# pico.net
KiCad netlist of a schematic drawn in EAGLE
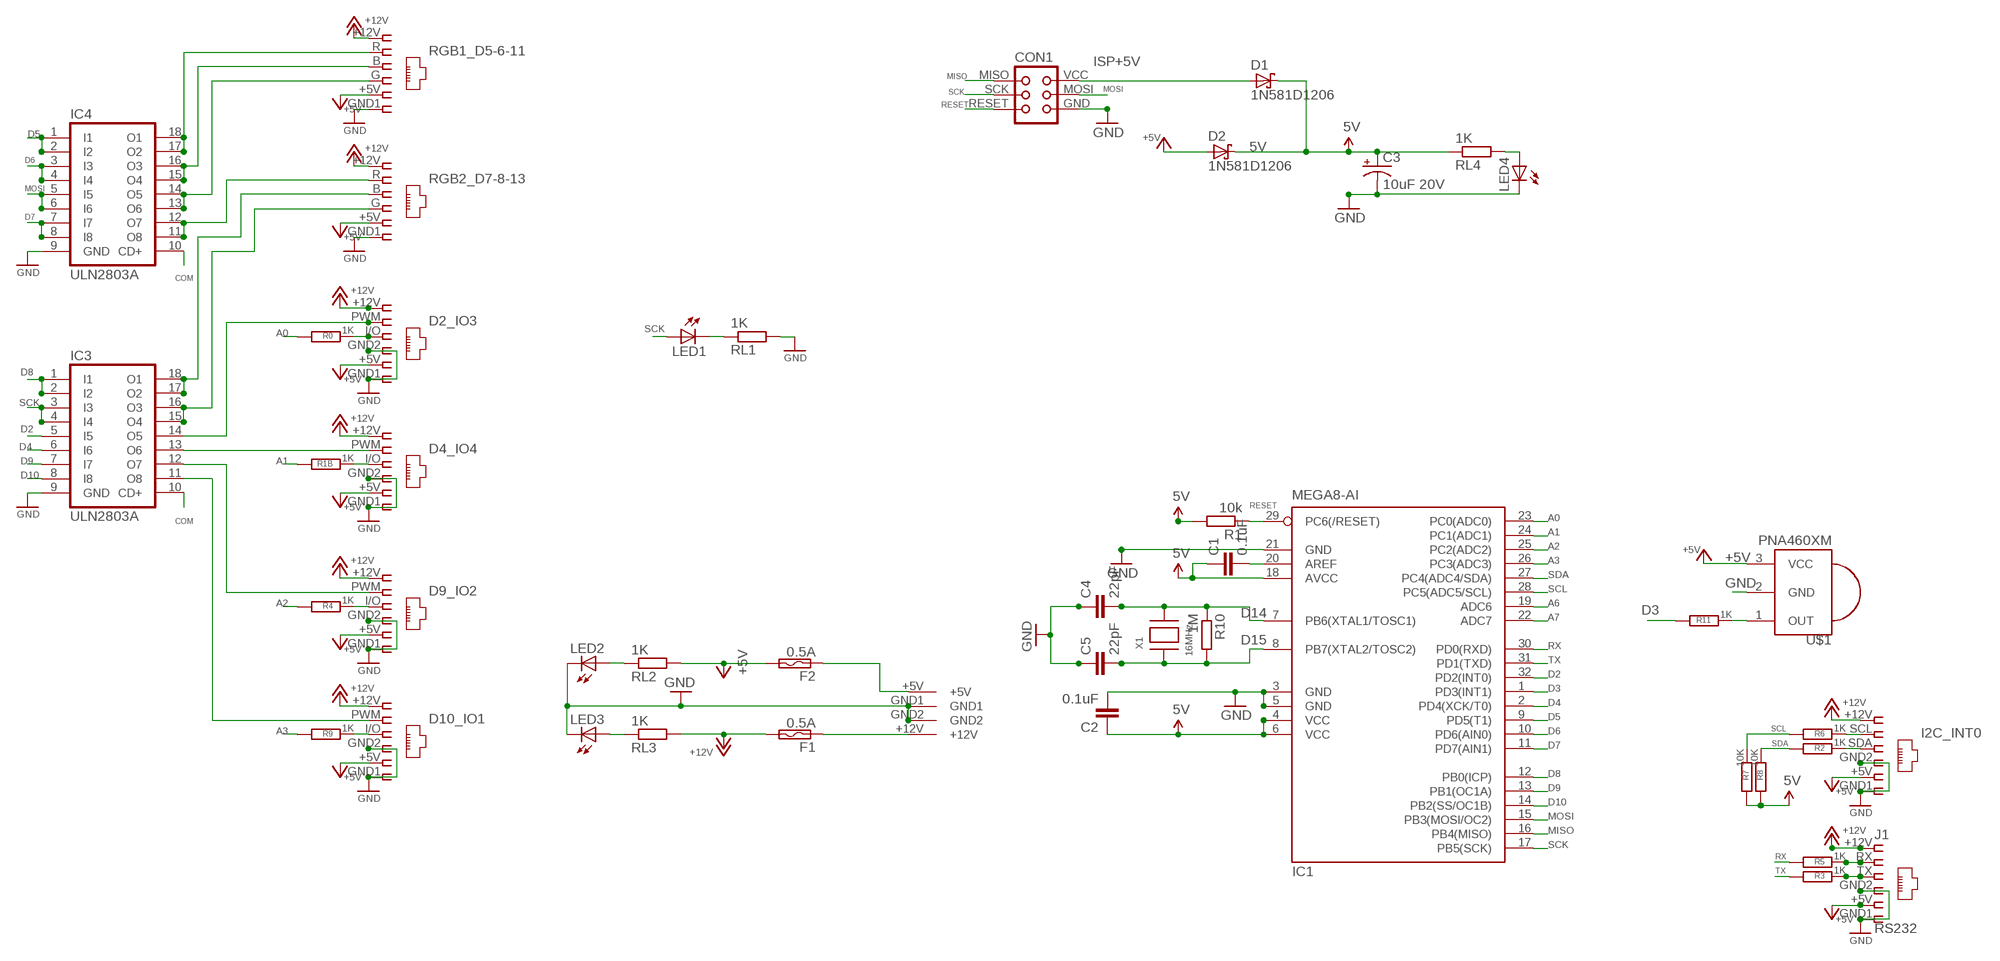
[diagram p0: schematic, sheet 1]

(export (version "E")
  (design (tool "Eeschema 10.0.6"))
  (components
    (comp (ref "C1")
      (value "0.1uF")
      (footprint "eagle-import:C1206")
      (libsource (lib "eagle-import") (part "C-EUC1206"))
    )
    (comp (ref "C2")
      (value "0.1uF")
      (footprint "eagle-import:C1206")
      (libsource (lib "eagle-import") (part "C-EUC1206"))
    )
    (comp (ref "C3")
      (value "10uF 20V")
      (footprint "eagle-import:EIA3216-KIT")
      (libsource (lib "eagle-import") (part "CAP_POL1206-KIT"))
    )
    (comp (ref "C4")
      (value "22pF")
      (footprint "eagle-import:C1206")
      (libsource (lib "eagle-import") (part "C-EUC1206"))
    )
    (comp (ref "C5")
      (value "22pF")
      (footprint "eagle-import:C1206")
      (libsource (lib "eagle-import") (part "C-EUC1206"))
    )
    (comp (ref "CON1")
      (value "TINYISP")
      (footprint "eagle-import:TINYISP")
      (libsource (lib "eagle-import") (part "TINYISP"))
    )
    (comp (ref "D1")
      (value "1N581D1206")
      (footprint "eagle-import:LED-1206")
      (libsource (lib "eagle-import") (part "1N581D1206"))
    )
    (comp (ref "D2")
      (value "1N581D1206")
      (footprint "eagle-import:LED-1206")
      (libsource (lib "eagle-import") (part "1N581D1206"))
    )
    (comp (ref "D2_IO3")
      (value "IO3")
      (footprint "eagle-import:RJ12-STRAIGHT")
      (libsource (lib "eagle-import") (part "RJ12STRAIGHT"))
    )
    (comp (ref "D4_IO4")
      (value "IO4")
      (footprint "eagle-import:RJ12-STRAIGHT")
      (libsource (lib "eagle-import") (part "RJ12STRAIGHT"))
    )
    (comp (ref "D9_IO2")
      (value "IO2")
      (footprint "eagle-import:RJ12-STRAIGHT")
      (libsource (lib "eagle-import") (part "RJ12STRAIGHT"))
    )
    (comp (ref "D10_IO1")
      (value "IO1")
      (footprint "eagle-import:RJ12-STRAIGHT")
      (libsource (lib "eagle-import") (part "RJ12STRAIGHT"))
    )
    (comp (ref "F1")
      (value "0.5A")
      (footprint "eagle-import:C1812")
      (libsource (lib "eagle-import") (part "POLYSWITCHSMD1812"))
    )
    (comp (ref "F2")
      (value "0.5A")
      (footprint "eagle-import:C1812")
      (libsource (lib "eagle-import") (part "POLYSWITCHSMD1812"))
    )
    (comp (ref "I2C_INT0")
      (value "I2C")
      (footprint "eagle-import:RJ12-STRAIGHT-I2C")
      (libsource (lib "eagle-import") (part "RJ12STRAIGHT-I2C"))
    )
    (comp (ref "IC1")
      (value "MEGA8-AI")
      (footprint "eagle-import:TQFP32-08")
      (fields (field (name "MPN") "ATMEGA8-16AU"))
      (libsource (lib "eagle-import") (part "MEGA8-AI"))
    )
    (comp (ref "IC3")
      (value "ULN2803A")
      (footprint "eagle-import:SO18W")
      (libsource (lib "eagle-import") (part "ULN2803A"))
    )
    (comp (ref "IC4")
      (value "ULN2803A")
      (footprint "eagle-import:SO18W")
      (libsource (lib "eagle-import") (part "ULN2803A"))
    )
    (comp (ref "J1")
      (value "RS232")
      (footprint "eagle-import:RJ12-STRAIGHT-RS232")
      (libsource (lib "eagle-import") (part "RJ12STRAIGHT-RS232-SERVER"))
    )
    (comp (ref "LED1")
      (value "LED3MM")
      (footprint "eagle-import:LED3MM")
      (libsource (lib "eagle-import") (part "LED3MM"))
    )
    (comp (ref "LED2")
      (value "LED3MM")
      (footprint "eagle-import:LED3MM")
      (libsource (lib "eagle-import") (part "LED3MM"))
    )
    (comp (ref "LED3")
      (value "LED3MM")
      (footprint "eagle-import:LED3MM")
      (libsource (lib "eagle-import") (part "LED3MM"))
    )
    (comp (ref "LED4")
      (value "LED3MM")
      (footprint "eagle-import:LED3MM")
      (libsource (lib "eagle-import") (part "LED3MM"))
    )
    (comp (ref "R0")
      (value "1K")
      (footprint "eagle-import:M1206")
      (libsource (lib "eagle-import") (part "R-EU_M1206"))
    )
    (comp (ref "R1")
      (value "10k")
      (footprint "eagle-import:M1206")
      (libsource (lib "eagle-import") (part "R-EU_M1206"))
    )
    (comp (ref "R1B")
      (value "1K")
      (footprint "eagle-import:M1206")
      (libsource (lib "eagle-import") (part "R-EU_M1206"))
    )
    (comp (ref "R2")
      (value "1K")
      (footprint "eagle-import:M1206")
      (libsource (lib "eagle-import") (part "R-EU_M1206"))
    )
    (comp (ref "R3")
      (value "1K")
      (footprint "eagle-import:M1206")
      (libsource (lib "eagle-import") (part "R-EU_M1206"))
    )
    (comp (ref "R4")
      (value "1K")
      (footprint "eagle-import:M1206")
      (libsource (lib "eagle-import") (part "R-EU_M1206"))
    )
    (comp (ref "R5")
      (value "1K")
      (footprint "eagle-import:M1206")
      (libsource (lib "eagle-import") (part "R-EU_M1206"))
    )
    (comp (ref "R6")
      (value "1K")
      (footprint "eagle-import:M1206")
      (libsource (lib "eagle-import") (part "R-EU_M1206"))
    )
    (comp (ref "R7")
      (value "10K")
      (footprint "eagle-import:M1206")
      (libsource (lib "eagle-import") (part "R-EU_M1206"))
    )
    (comp (ref "R8")
      (value "10K")
      (footprint "eagle-import:M1206")
      (libsource (lib "eagle-import") (part "R-EU_M1206"))
    )
    (comp (ref "R9")
      (value "1K")
      (footprint "eagle-import:M1206")
      (libsource (lib "eagle-import") (part "R-EU_M1206"))
    )
    (comp (ref "R10")
      (value "1M")
      (footprint "eagle-import:M1206")
      (libsource (lib "eagle-import") (part "R-EU_M1206"))
    )
    (comp (ref "R11")
      (value "1K")
      (footprint "eagle-import:M1206")
      (libsource (lib "eagle-import") (part "R-EU_M1206"))
    )
    (comp (ref "RGB1_D5-6-11")
      (value "RGB1")
      (footprint "eagle-import:RJ12-STRAIGHT-RGB")
      (libsource (lib "eagle-import") (part "RJ12STRAIGHT-RGB"))
    )
    (comp (ref "RGB2_D7-8-13")
      (value "RGB2")
      (footprint "eagle-import:RJ12-STRAIGHT-RGB")
      (libsource (lib "eagle-import") (part "RJ12STRAIGHT-RGB"))
    )
    (comp (ref "RL1")
      (value "1K")
      (footprint "eagle-import:M1206")
      (libsource (lib "eagle-import") (part "R-EU_M1206"))
    )
    (comp (ref "RL2")
      (value "1K")
      (footprint "eagle-import:M1206")
      (libsource (lib "eagle-import") (part "R-EU_M1206"))
    )
    (comp (ref "RL3")
      (value "1K")
      (footprint "eagle-import:M1206")
      (libsource (lib "eagle-import") (part "R-EU_M1206"))
    )
    (comp (ref "RL4")
      (value "1K")
      (footprint "eagle-import:M1206")
      (libsource (lib "eagle-import") (part "R-EU_M1206"))
    )
    (comp (ref "U$1")
      (value "PNA460XM")
      (footprint "eagle-import:PNA460XM")
      (libsource (lib "eagle-import") (part "PNA460XM"))
    )
    (comp (ref "U$2")
      (value "KPJX-4S-S")
      (footprint "eagle-import:KPJX-4S-S")
      (libsource (lib "eagle-import") (part "KPJX-4S-S"))
    )
    (comp (ref "X1")
      (value "16MHz")
      (footprint "eagle-import:NX6035")
      (libsource (lib "eagle-import") (part "XTALNX6035"))
    )
  )
  (nets
    (net (code "1") (name "+5V") (class "Default")
      (node (ref "D10_IO1") (pin "+5V") (pinfunction "5_+5V") (pintype "power_in"))
      (node (ref "D2") (pin "A") (pinfunction "A_A") (pintype "passive"))
      (node (ref "D2_IO3") (pin "+5V") (pinfunction "5_+5V") (pintype "power_in"))
      (node (ref "D4_IO4") (pin "+5V") (pinfunction "5_+5V") (pintype "power_in"))
      (node (ref "D9_IO2") (pin "+5V") (pinfunction "5_+5V") (pintype "power_in"))
      (node (ref "F2") (pin "2") (pinfunction "2_2") (pintype "passive"))
      (node (ref "I2C_INT0") (pin "+5V") (pinfunction "5_+5V") (pintype "power_in"))
      (node (ref "J1") (pin "+5V") (pinfunction "5_+5V") (pintype "power_in"))
      (node (ref "RGB1_D5-6-11") (pin "+5V") (pinfunction "5_+5V") (pintype "power_in"))
      (node (ref "RGB2_D7-8-13") (pin "+5V") (pinfunction "5_+5V") (pintype "power_in"))
      (node (ref "RL2") (pin "2") (pinfunction "2_2") (pintype "passive"))
      (node (ref "U$1") (pin "3") (pinfunction "VCC_3") (pintype "power_in"))
    )
    (net (code "2") (name "+12V") (class "Default")
      (node (ref "D10_IO1") (pin "+12V") (pinfunction "1_+12V") (pintype "power_in"))
      (node (ref "D2_IO3") (pin "+12V") (pinfunction "1_+12V") (pintype "power_in"))
      (node (ref "D4_IO4") (pin "+12V") (pinfunction "1_+12V") (pintype "power_in"))
      (node (ref "D9_IO2") (pin "+12V") (pinfunction "1_+12V") (pintype "power_in"))
      (node (ref "F1") (pin "2") (pinfunction "2_2") (pintype "passive"))
      (node (ref "I2C_INT0") (pin "+12V") (pinfunction "1_+12V") (pintype "power_in"))
      (node (ref "J1") (pin "+12V") (pinfunction "1_+12V") (pintype "power_in"))
      (node (ref "RGB1_D5-6-11") (pin "+12V") (pinfunction "1_+12V") (pintype "power_in"))
      (node (ref "RGB2_D7-8-13") (pin "+12V") (pinfunction "1_+12V") (pintype "power_in"))
      (node (ref "RL3") (pin "2") (pinfunction "2_2") (pintype "passive"))
    )
    (net (code "3") (name "/A0") (class "Default")
      (node (ref "IC1") (pin "23") (pinfunction "PC0(ADC0)_23") (pintype "bidirectional"))
      (node (ref "R0") (pin "2") (pinfunction "2_2") (pintype "passive"))
    )
    (net (code "4") (name "/A1") (class "Default")
      (node (ref "IC1") (pin "24") (pinfunction "PC1(ADC1)_24") (pintype "bidirectional"))
      (node (ref "R1B") (pin "2") (pinfunction "2_2") (pintype "passive"))
    )
    (net (code "5") (name "/A2") (class "Default")
      (node (ref "IC1") (pin "25") (pinfunction "PC2(ADC2)_25") (pintype "bidirectional"))
      (node (ref "R4") (pin "2") (pinfunction "2_2") (pintype "passive"))
    )
    (net (code "6") (name "/A3") (class "Default")
      (node (ref "IC1") (pin "26") (pinfunction "PC3(ADC3)_26") (pintype "bidirectional"))
      (node (ref "R9") (pin "2") (pinfunction "2_2") (pintype "passive"))
    )
    (net (code "7") (name "/A6") (class "Default")
      (node (ref "IC1") (pin "19") (pinfunction "ADC6_19") (pintype "bidirectional"))
    )
    (net (code "8") (name "/A7") (class "Default")
      (node (ref "IC1") (pin "22") (pinfunction "ADC7_22") (pintype "bidirectional"))
    )
    (net (code "9") (name "/COM") (class "Default")
      (node (ref "IC3") (pin "10") (pinfunction "CD+_10") (pintype "passive"))
      (node (ref "IC4") (pin "10") (pinfunction "CD+_10") (pintype "passive"))
    )
    (net (code "10") (name "/D2") (class "Default")
      (node (ref "IC1") (pin "32") (pinfunction "PD2(INT0)_32") (pintype "bidirectional"))
      (node (ref "IC3") (pin "5") (pinfunction "I5_5") (pintype "input"))
    )
    (net (code "11") (name "/D3") (class "Default")
      (node (ref "IC1") (pin "1") (pinfunction "PD3(INT1)_1") (pintype "bidirectional"))
      (node (ref "R11") (pin "2") (pinfunction "2_2") (pintype "passive"))
    )
    (net (code "12") (name "/D4") (class "Default")
      (node (ref "IC1") (pin "2") (pinfunction "PD4(XCK/T0)_2") (pintype "bidirectional"))
      (node (ref "IC3") (pin "6") (pinfunction "I6_6") (pintype "input"))
    )
    (net (code "13") (name "/D5") (class "Default")
      (node (ref "IC1") (pin "9") (pinfunction "PD5(T1)_9") (pintype "bidirectional"))
      (node (ref "IC4") (pin "1") (pinfunction "I1_1") (pintype "input"))
      (node (ref "IC4") (pin "2") (pinfunction "I2_2") (pintype "input"))
    )
    (net (code "14") (name "/D6") (class "Default")
      (node (ref "IC1") (pin "10") (pinfunction "PD6(AIN0)_10") (pintype "bidirectional"))
      (node (ref "IC4") (pin "3") (pinfunction "I3_3") (pintype "input"))
      (node (ref "IC4") (pin "4") (pinfunction "I4_4") (pintype "input"))
    )
    (net (code "15") (name "/D7") (class "Default")
      (node (ref "IC1") (pin "11") (pinfunction "PD7(AIN1)_11") (pintype "bidirectional"))
      (node (ref "IC4") (pin "7") (pinfunction "I7_7") (pintype "input"))
      (node (ref "IC4") (pin "8") (pinfunction "I8_8") (pintype "input"))
    )
    (net (code "16") (name "/D8") (class "Default")
      (node (ref "IC1") (pin "12") (pinfunction "PB0(ICP)_12") (pintype "bidirectional"))
      (node (ref "IC3") (pin "1") (pinfunction "I1_1") (pintype "input"))
      (node (ref "IC3") (pin "2") (pinfunction "I2_2") (pintype "input"))
    )
    (net (code "17") (name "/D9") (class "Default")
      (node (ref "IC1") (pin "13") (pinfunction "PB1(OC1A)_13") (pintype "bidirectional"))
      (node (ref "IC3") (pin "7") (pinfunction "I7_7") (pintype "input"))
    )
    (net (code "18") (name "/D10") (class "Default")
      (node (ref "IC1") (pin "14") (pinfunction "PB2(SS/OC1B)_14") (pintype "bidirectional"))
      (node (ref "IC3") (pin "8") (pinfunction "I8_8") (pintype "input"))
    )
    (net (code "19") (name "/D14") (class "Default")
      (node (ref "C4") (pin "2") (pinfunction "2_2") (pintype "passive"))
      (node (ref "IC1") (pin "7") (pinfunction "PB6(XTAL1/TOSC1)_7") (pintype "bidirectional"))
      (node (ref "R10") (pin "1") (pinfunction "1_1") (pintype "passive"))
      (node (ref "X1") (pin "P$2") (pinfunction "P$2_P$2") (pintype "bidirectional"))
    )
    (net (code "20") (name "/D15") (class "Default")
      (node (ref "C5") (pin "2") (pinfunction "2_2") (pintype "passive"))
      (node (ref "IC1") (pin "8") (pinfunction "PB7(XTAL2/TOSC2)_8") (pintype "bidirectional"))
      (node (ref "R10") (pin "2") (pinfunction "2_2") (pintype "passive"))
      (node (ref "X1") (pin "P$1") (pinfunction "P$1_P$1") (pintype "bidirectional"))
    )
    (net (code "21") (name "/ISP+5V") (class "Default")
      (node (ref "CON1") (pin "VCC") (pinfunction "VCC_VCC") (pintype "passive"))
      (node (ref "D1") (pin "A") (pinfunction "A_A") (pintype "passive"))
    )
    (net (code "22") (name "/MISO") (class "Default")
      (node (ref "CON1") (pin "MISO") (pinfunction "MISO_MISO") (pintype "passive"))
      (node (ref "IC1") (pin "16") (pinfunction "PB4(MISO)_16") (pintype "bidirectional"))
    )
    (net (code "23") (name "/MOSI") (class "Default")
      (node (ref "CON1") (pin "MOSI") (pinfunction "MOSI_MOSI") (pintype "passive"))
      (node (ref "IC1") (pin "15") (pinfunction "PB3(MOSI/OC2)_15") (pintype "bidirectional"))
      (node (ref "IC4") (pin "5") (pinfunction "I5_5") (pintype "input"))
      (node (ref "IC4") (pin "6") (pinfunction "I6_6") (pintype "input"))
    )
    (net (code "24") (name "/RESET") (class "Default")
      (node (ref "CON1") (pin "RESET") (pinfunction "RESET_RESET") (pintype "passive"))
      (node (ref "IC1") (pin "29") (pinfunction "PC6(/RESET)_29") (pintype "bidirectional"))
      (node (ref "R1") (pin "1") (pinfunction "1_1") (pintype "passive"))
    )
    (net (code "25") (name "/RX") (class "Default")
      (node (ref "IC1") (pin "30") (pinfunction "PD0(RXD)_30") (pintype "bidirectional"))
      (node (ref "R5") (pin "2") (pinfunction "2_2") (pintype "passive"))
    )
    (net (code "26") (name "/SCK") (class "Default")
      (node (ref "CON1") (pin "SCK") (pinfunction "SCK_SCK") (pintype "passive"))
      (node (ref "IC1") (pin "17") (pinfunction "PB5(SCK)_17") (pintype "bidirectional"))
      (node (ref "IC3") (pin "3") (pinfunction "I3_3") (pintype "input"))
      (node (ref "IC3") (pin "4") (pinfunction "I4_4") (pintype "input"))
      (node (ref "LED1") (pin "A") (pinfunction "A_A") (pintype "passive"))
    )
    (net (code "27") (name "/SCL") (class "Default")
      (node (ref "IC1") (pin "28") (pinfunction "PC5(ADC5/SCL)_28") (pintype "bidirectional"))
      (node (ref "R6") (pin "2") (pinfunction "2_2") (pintype "passive"))
      (node (ref "R7") (pin "1") (pinfunction "1_1") (pintype "passive"))
    )
    (net (code "28") (name "/SDA") (class "Default")
      (node (ref "IC1") (pin "27") (pinfunction "PC4(ADC4/SDA)_27") (pintype "bidirectional"))
      (node (ref "R2") (pin "2") (pinfunction "2_2") (pintype "passive"))
      (node (ref "R8") (pin "1") (pinfunction "1_1") (pintype "passive"))
    )
    (net (code "29") (name "/TX") (class "Default")
      (node (ref "IC1") (pin "31") (pinfunction "PD1(TXD)_31") (pintype "bidirectional"))
      (node (ref "R3") (pin "2") (pinfunction "2_2") (pintype "passive"))
    )
    (net (code "30") (name "5V") (class "Default")
      (node (ref "C1") (pin "1") (pinfunction "1_1") (pintype "passive"))
      (node (ref "C2") (pin "1") (pinfunction "1_1") (pintype "passive"))
      (node (ref "C3") (pin "A") (pinfunction "+_A") (pintype "passive"))
      (node (ref "D1") (pin "C") (pinfunction "C_C") (pintype "passive"))
      (node (ref "D2") (pin "C") (pinfunction "C_C") (pintype "passive"))
      (node (ref "IC1") (pin "18") (pinfunction "AVCC_18") (pintype "power_in"))
      (node (ref "IC1") (pin "4") (pinfunction "VCC_4") (pintype "power_in"))
      (node (ref "IC1") (pin "6") (pinfunction "VCC_6") (pintype "power_in"))
      (node (ref "R1") (pin "2") (pinfunction "2_2") (pintype "passive"))
      (node (ref "R7") (pin "2") (pinfunction "2_2") (pintype "passive"))
      (node (ref "R8") (pin "2") (pinfunction "2_2") (pintype "passive"))
      (node (ref "RL4") (pin "1") (pinfunction "1_1") (pintype "passive"))
    )
    (net (code "31") (name "GND") (class "Default")
      (node (ref "C2") (pin "2") (pinfunction "2_2") (pintype "passive"))
      (node (ref "C3") (pin "C") (pinfunction "-_C") (pintype "passive"))
      (node (ref "C4") (pin "1") (pinfunction "1_1") (pintype "passive"))
      (node (ref "C5") (pin "1") (pinfunction "1_1") (pintype "passive"))
      (node (ref "CON1") (pin "GND") (pinfunction "GND_GND") (pintype "passive"))
      (node (ref "D10_IO1") (pin "GND1") (pinfunction "6_GND1") (pintype "power_in"))
      (node (ref "D10_IO1") (pin "GND2") (pinfunction "4_GND2") (pintype "power_in"))
      (node (ref "D2_IO3") (pin "GND1") (pinfunction "6_GND1") (pintype "power_in"))
      (node (ref "D2_IO3") (pin "GND2") (pinfunction "4_GND2") (pintype "power_in"))
      (node (ref "D4_IO4") (pin "GND1") (pinfunction "6_GND1") (pintype "power_in"))
      (node (ref "D4_IO4") (pin "GND2") (pinfunction "4_GND2") (pintype "power_in"))
      (node (ref "D9_IO2") (pin "GND1") (pinfunction "6_GND1") (pintype "power_in"))
      (node (ref "D9_IO2") (pin "GND2") (pinfunction "4_GND2") (pintype "power_in"))
      (node (ref "I2C_INT0") (pin "GND1") (pinfunction "6_GND1") (pintype "power_in"))
      (node (ref "I2C_INT0") (pin "GND2") (pinfunction "4_GND2") (pintype "power_in"))
      (node (ref "IC1") (pin "21") (pinfunction "GND_21") (pintype "power_in"))
      (node (ref "IC1") (pin "3") (pinfunction "GND_3") (pintype "power_in"))
      (node (ref "IC1") (pin "5") (pinfunction "GND_5") (pintype "power_in"))
      (node (ref "IC3") (pin "9") (pinfunction "GND_9") (pintype "power_in"))
      (node (ref "IC4") (pin "9") (pinfunction "GND_9") (pintype "power_in"))
      (node (ref "J1") (pin "GND1") (pinfunction "6_GND1") (pintype "power_in"))
      (node (ref "J1") (pin "GND2") (pinfunction "4_GND2") (pintype "power_in"))
      (node (ref "LED2") (pin "K") (pinfunction "C_K") (pintype "passive"))
      (node (ref "LED3") (pin "K") (pinfunction "C_K") (pintype "passive"))
      (node (ref "LED4") (pin "K") (pinfunction "C_K") (pintype "passive"))
      (node (ref "RGB1_D5-6-11") (pin "GND1") (pinfunction "6_GND1") (pintype "power_in"))
      (node (ref "RGB2_D7-8-13") (pin "GND1") (pinfunction "6_GND1") (pintype "power_in"))
      (node (ref "RL1") (pin "2") (pinfunction "2_2") (pintype "passive"))
      (node (ref "U$1") (pin "2") (pinfunction "GND_2") (pintype "power_in"))
      (node (ref "U$2") (pin "GND1") (pinfunction "GND1_GND1") (pintype "input"))
      (node (ref "U$2") (pin "GND2") (pinfunction "GND2_GND2") (pintype "input"))
    )
    (net (code "32") (name "Net-(D2_IO3-2)") (class "Default")
      (node (ref "D2_IO3") (pin "PWM") (pinfunction "2_PWM") (pintype "bidirectional"))
      (node (ref "IC3") (pin "14") (pinfunction "O5_14") (pintype "open_collector"))
    )
    (net (code "33") (name "Net-(D2_IO3-3)") (class "Default")
      (node (ref "D2_IO3") (pin "I/O") (pinfunction "3_I/O") (pintype "bidirectional"))
      (node (ref "R0") (pin "1") (pinfunction "1_1") (pintype "passive"))
    )
    (net (code "34") (name "Net-(D4_IO4-2)") (class "Default")
      (node (ref "D4_IO4") (pin "PWM") (pinfunction "2_PWM") (pintype "bidirectional"))
      (node (ref "IC3") (pin "13") (pinfunction "O6_13") (pintype "open_collector"))
    )
    (net (code "35") (name "Net-(D4_IO4-3)") (class "Default")
      (node (ref "D4_IO4") (pin "I/O") (pinfunction "3_I/O") (pintype "bidirectional"))
      (node (ref "R1B") (pin "1") (pinfunction "1_1") (pintype "passive"))
    )
    (net (code "36") (name "Net-(D9_IO2-2)") (class "Default")
      (node (ref "D9_IO2") (pin "PWM") (pinfunction "2_PWM") (pintype "bidirectional"))
      (node (ref "IC3") (pin "12") (pinfunction "O7_12") (pintype "open_collector"))
    )
    (net (code "37") (name "Net-(D9_IO2-3)") (class "Default")
      (node (ref "D9_IO2") (pin "I/O") (pinfunction "3_I/O") (pintype "bidirectional"))
      (node (ref "R4") (pin "1") (pinfunction "1_1") (pintype "passive"))
    )
    (net (code "38") (name "Net-(D10_IO1-2)") (class "Default")
      (node (ref "D10_IO1") (pin "PWM") (pinfunction "2_PWM") (pintype "bidirectional"))
      (node (ref "IC3") (pin "11") (pinfunction "O8_11") (pintype "open_collector"))
    )
    (net (code "39") (name "Net-(D10_IO1-3)") (class "Default")
      (node (ref "D10_IO1") (pin "I/O") (pinfunction "3_I/O") (pintype "bidirectional"))
      (node (ref "R9") (pin "1") (pinfunction "1_1") (pintype "passive"))
    )
    (net (code "40") (name "Net-(F1-Pad1)") (class "Default")
      (node (ref "F1") (pin "1") (pinfunction "1_1") (pintype "passive"))
      (node (ref "U$2") (pin "+12V") (pinfunction "+12V_+12V") (pintype "power_in"))
    )
    (net (code "41") (name "Net-(F2-Pad1)") (class "Default")
      (node (ref "F2") (pin "1") (pinfunction "1_1") (pintype "passive"))
      (node (ref "U$2") (pin "+5V") (pinfunction "+5V_+5V") (pintype "power_in"))
    )
    (net (code "42") (name "Net-(I2C_INT0-2)") (class "Default")
      (node (ref "I2C_INT0") (pin "SCL") (pinfunction "2_SCL") (pintype "bidirectional"))
      (node (ref "R6") (pin "1") (pinfunction "1_1") (pintype "passive"))
    )
    (net (code "43") (name "Net-(I2C_INT0-3)") (class "Default")
      (node (ref "I2C_INT0") (pin "SDA") (pinfunction "3_SDA") (pintype "bidirectional"))
      (node (ref "R2") (pin "1") (pinfunction "1_1") (pintype "passive"))
    )
    (net (code "44") (name "Net-(IC1-AREF)") (class "Default")
      (node (ref "C1") (pin "2") (pinfunction "2_2") (pintype "passive"))
      (node (ref "IC1") (pin "20") (pinfunction "AREF_20") (pintype "passive"))
    )
    (net (code "45") (name "Net-(IC3-O1)") (class "Default")
      (node (ref "IC3") (pin "17") (pinfunction "O2_17") (pintype "open_collector"))
      (node (ref "IC3") (pin "18") (pinfunction "O1_18") (pintype "open_collector"))
      (node (ref "RGB2_D7-8-13") (pin "B") (pinfunction "3_B") (pintype "bidirectional"))
    )
    (net (code "46") (name "Net-(IC3-O3)") (class "Default")
      (node (ref "IC3") (pin "15") (pinfunction "O4_15") (pintype "open_collector"))
      (node (ref "IC3") (pin "16") (pinfunction "O3_16") (pintype "open_collector"))
      (node (ref "RGB2_D7-8-13") (pin "G") (pinfunction "4_G") (pintype "power_in"))
    )
    (net (code "47") (name "Net-(IC4-O1)") (class "Default")
      (node (ref "IC4") (pin "17") (pinfunction "O2_17") (pintype "open_collector"))
      (node (ref "IC4") (pin "18") (pinfunction "O1_18") (pintype "open_collector"))
      (node (ref "RGB1_D5-6-11") (pin "R") (pinfunction "2_R") (pintype "bidirectional"))
    )
    (net (code "48") (name "Net-(IC4-O3)") (class "Default")
      (node (ref "IC4") (pin "15") (pinfunction "O4_15") (pintype "open_collector"))
      (node (ref "IC4") (pin "16") (pinfunction "O3_16") (pintype "open_collector"))
      (node (ref "RGB1_D5-6-11") (pin "B") (pinfunction "3_B") (pintype "bidirectional"))
    )
    (net (code "49") (name "Net-(IC4-O5)") (class "Default")
      (node (ref "IC4") (pin "13") (pinfunction "O6_13") (pintype "open_collector"))
      (node (ref "IC4") (pin "14") (pinfunction "O5_14") (pintype "open_collector"))
      (node (ref "RGB1_D5-6-11") (pin "G") (pinfunction "4_G") (pintype "power_in"))
    )
    (net (code "50") (name "Net-(IC4-O7)") (class "Default")
      (node (ref "IC4") (pin "11") (pinfunction "O8_11") (pintype "open_collector"))
      (node (ref "IC4") (pin "12") (pinfunction "O7_12") (pintype "open_collector"))
      (node (ref "RGB2_D7-8-13") (pin "R") (pinfunction "2_R") (pintype "bidirectional"))
    )
    (net (code "51") (name "Net-(J1-2)") (class "Default")
      (node (ref "J1") (pin "RX") (pinfunction "2_RX") (pintype "bidirectional"))
      (node (ref "R5") (pin "1") (pinfunction "1_1") (pintype "passive"))
    )
    (net (code "52") (name "Net-(J1-3)") (class "Default")
      (node (ref "J1") (pin "TX") (pinfunction "3_TX") (pintype "bidirectional"))
      (node (ref "R3") (pin "1") (pinfunction "1_1") (pintype "passive"))
    )
    (net (code "53") (name "Net-(LED1-C)") (class "Default")
      (node (ref "LED1") (pin "K") (pinfunction "C_K") (pintype "passive"))
      (node (ref "RL1") (pin "1") (pinfunction "1_1") (pintype "passive"))
    )
    (net (code "54") (name "Net-(LED2-PadA)") (class "Default")
      (node (ref "LED2") (pin "A") (pinfunction "A_A") (pintype "passive"))
      (node (ref "RL2") (pin "1") (pinfunction "1_1") (pintype "passive"))
    )
    (net (code "55") (name "Net-(LED3-PadA)") (class "Default")
      (node (ref "LED3") (pin "A") (pinfunction "A_A") (pintype "passive"))
      (node (ref "RL3") (pin "1") (pinfunction "1_1") (pintype "passive"))
    )
    (net (code "56") (name "Net-(LED4-PadA)") (class "Default")
      (node (ref "LED4") (pin "A") (pinfunction "A_A") (pintype "passive"))
      (node (ref "RL4") (pin "2") (pinfunction "2_2") (pintype "passive"))
    )
    (net (code "57") (name "Net-(U$1-OUT)") (class "Default")
      (node (ref "R11") (pin "1") (pinfunction "1_1") (pintype "passive"))
      (node (ref "U$1") (pin "1") (pinfunction "OUT_1") (pintype "output"))
    )
  )
)
